# HeatpumpMonitor.net
KiCad netlist of a schematic drawn in EAGLE
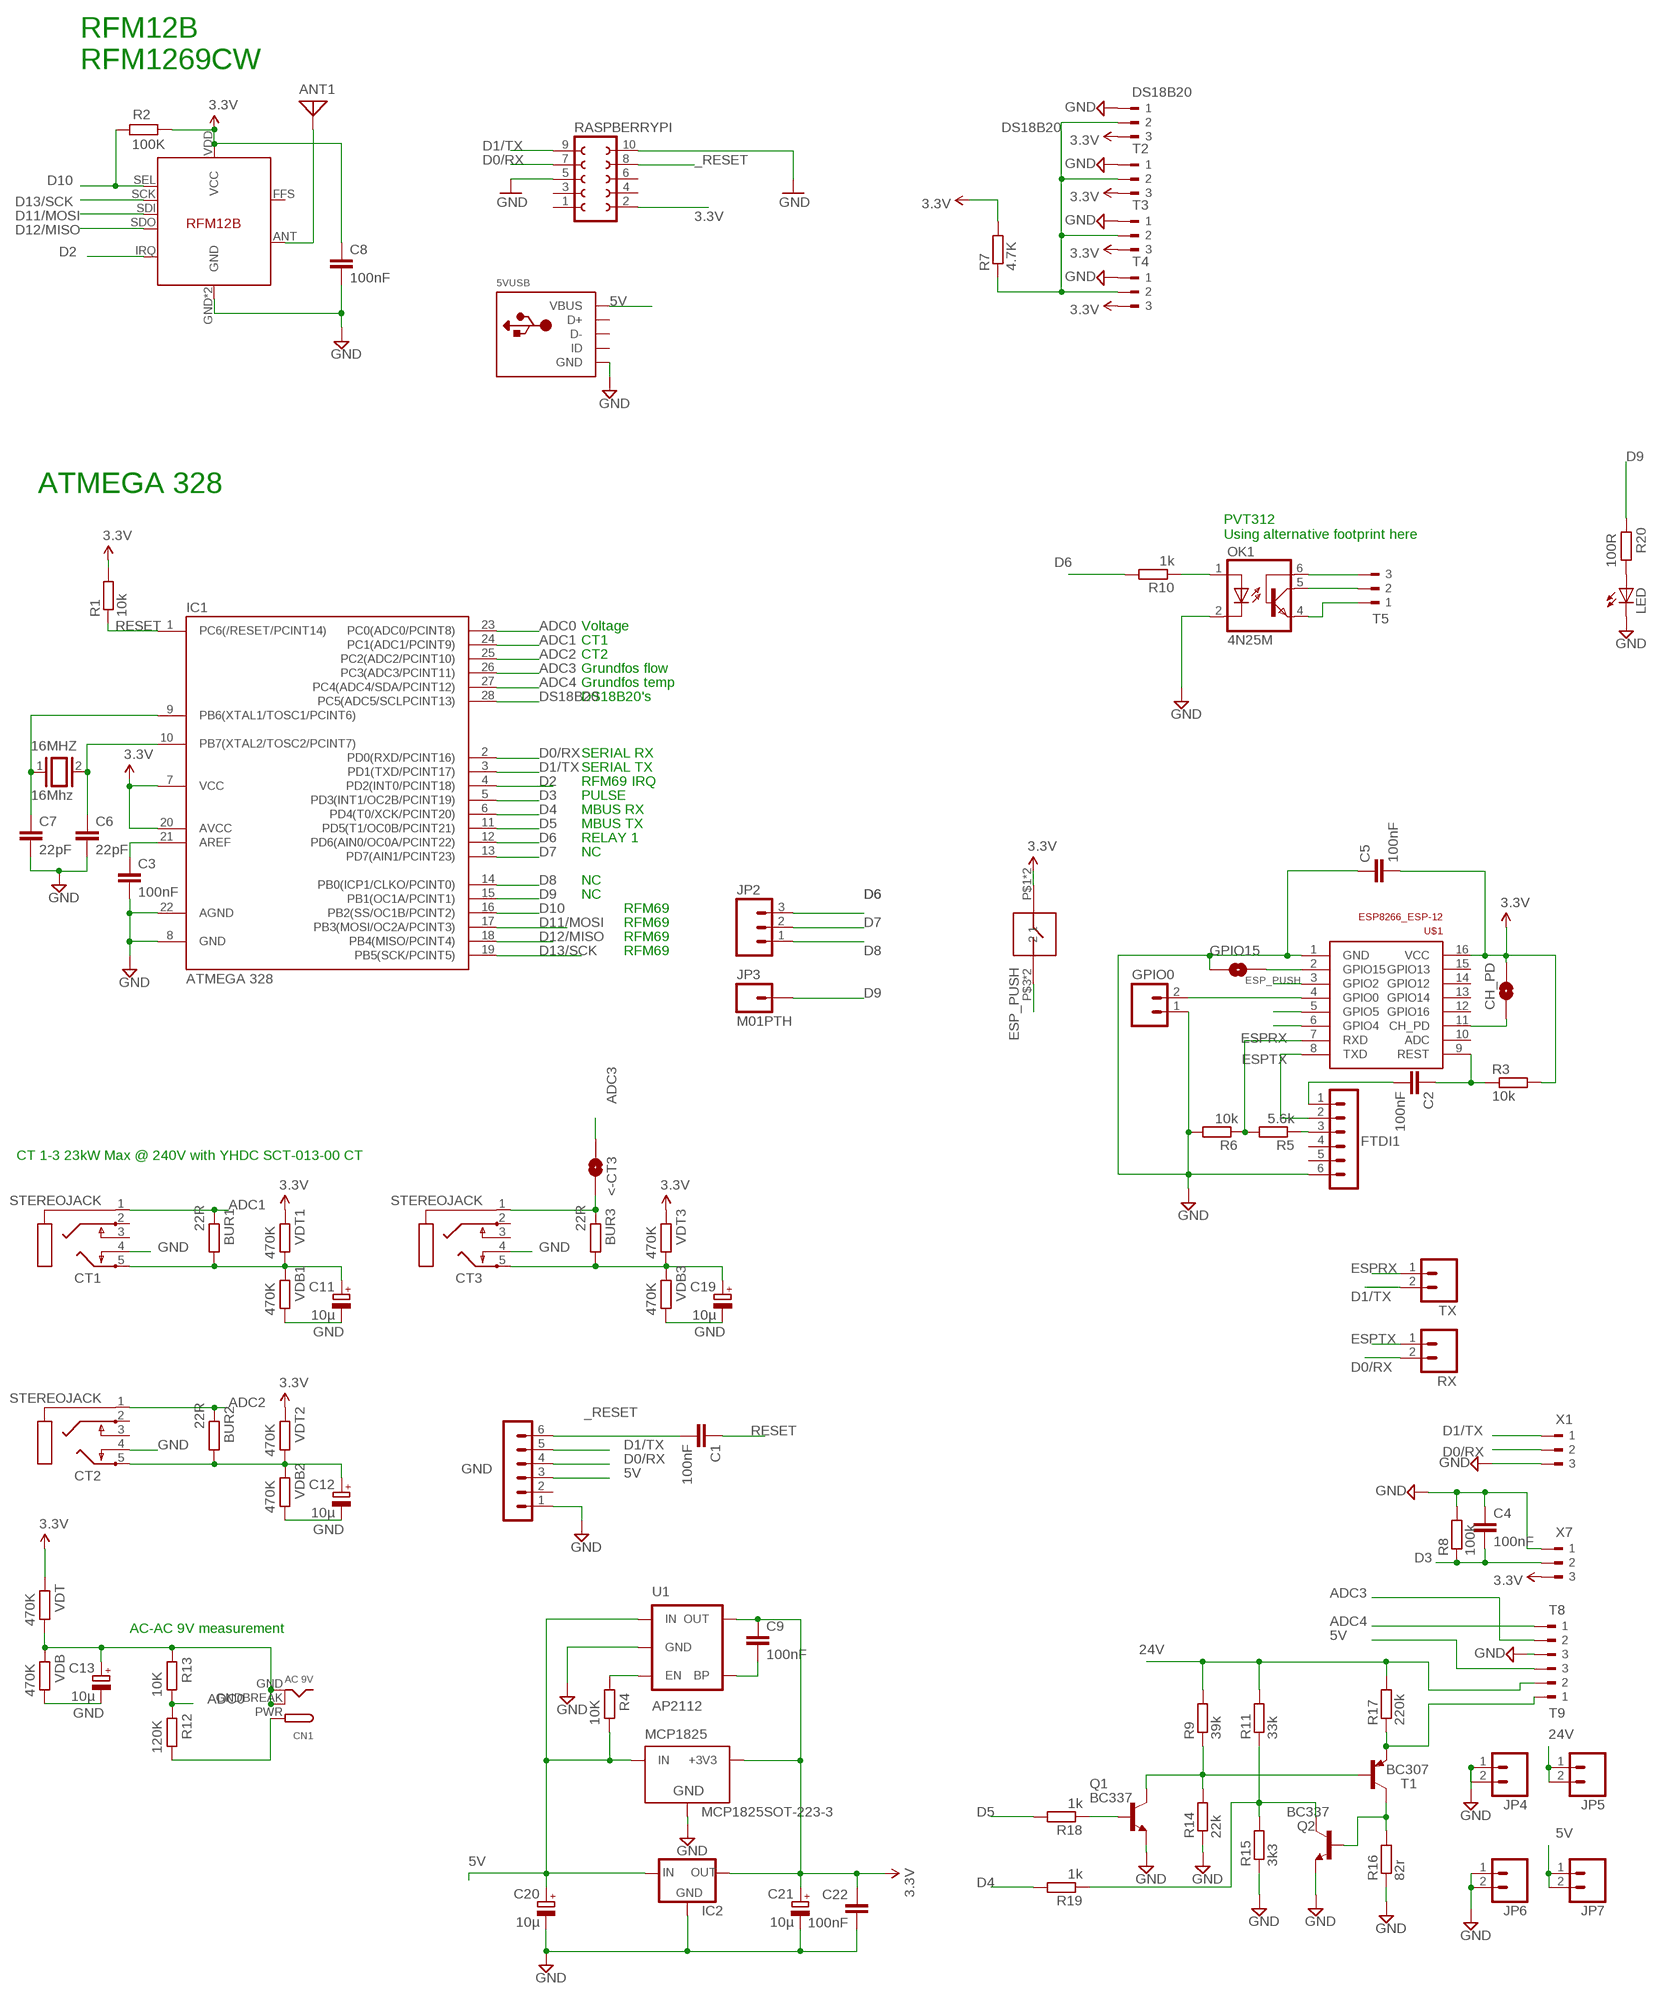
[diagram p0: schematic, sheet 1]

(export (version "E")
  (design (tool "Eeschema 10.0.6"))
  (components
    (comp (ref "5VUSB")
      (value "USBMOLEX")
      (footprint "eagle-import:USB-MINIB-THM-MOLEX")
      (libsource (lib "eagle-import") (part "USBMOLEX"))
    )
    (comp (ref "16MHZ")
      (value "16Mhz")
      (footprint "eagle-import:QS")
      (libsource (lib "eagle-import") (part "XTAL/S"))
    )
    (comp (ref "<-CT3")
      (value "SOLDERJUMPERNO")
      (footprint "eagle-import:SJ_2S-NO")
      (libsource (lib "eagle-import") (part "SOLDERJUMPERNO"))
    )
    (comp (ref "ANT1")
      (value "ANTENNA")
      (footprint "eagle-import:PAD-01")
      (libsource (lib "eagle-import") (part "ANTENNA"))
    )
    (comp (ref "BUR1")
      (value "22R")
      (footprint "eagle-import:0204_7")
      (libsource (lib "eagle-import") (part "R-EU_0204/7"))
    )
    (comp (ref "BUR2")
      (value "22R")
      (footprint "eagle-import:0204_7")
      (libsource (lib "eagle-import") (part "R-EU_0204/7"))
    )
    (comp (ref "BUR3")
      (value "22R")
      (footprint "eagle-import:0204_7")
      (libsource (lib "eagle-import") (part "R-EU_0204/7"))
    )
    (comp (ref "C1")
      (value "100nF")
      (footprint "eagle-import:C025-024X044")
      (libsource (lib "eagle-import") (part "C-EU025-024X044"))
    )
    (comp (ref "C2")
      (value "100nF")
      (footprint "eagle-import:C025-024X044")
      (libsource (lib "eagle-import") (part "C-EU025-024X044"))
    )
    (comp (ref "C3")
      (value "100nF")
      (footprint "eagle-import:C025-024X044")
      (libsource (lib "eagle-import") (part "C-EU025-024X044"))
    )
    (comp (ref "C4")
      (value "100nF")
      (footprint "eagle-import:C025-024X044")
      (libsource (lib "eagle-import") (part "C-EU025-024X044"))
    )
    (comp (ref "C5")
      (value "100nF")
      (footprint "eagle-import:C025-024X044")
      (libsource (lib "eagle-import") (part "C-EU025-024X044"))
    )
    (comp (ref "C6")
      (value "22pF")
      (footprint "eagle-import:C2.5-2")
      (libsource (lib "eagle-import") (part "C2.5/2"))
    )
    (comp (ref "C7")
      (value "22pF")
      (footprint "eagle-import:C2.5-2")
      (libsource (lib "eagle-import") (part "C2.5/2"))
    )
    (comp (ref "C8")
      (value "100nF")
      (footprint "eagle-import:C025-024X044")
      (libsource (lib "eagle-import") (part "C-EU025-024X044"))
    )
    (comp (ref "C9")
      (value "100nF")
      (footprint "eagle-import:C0603")
      (libsource (lib "eagle-import") (part "C-EUC0603"))
    )
    (comp (ref "C11")
      (value "10µ")
      (footprint "eagle-import:E1,8-4")
      (libsource (lib "eagle-import") (part "CPOL-EUE1.8-4"))
    )
    (comp (ref "C12")
      (value "10µ")
      (footprint "eagle-import:E1,8-4")
      (libsource (lib "eagle-import") (part "CPOL-EUE1.8-4"))
    )
    (comp (ref "C13")
      (value "10µ")
      (footprint "eagle-import:E1,8-4")
      (libsource (lib "eagle-import") (part "CPOL-EUE1.8-4"))
    )
    (comp (ref "C19")
      (value "10µ")
      (footprint "eagle-import:E1,8-4")
      (libsource (lib "eagle-import") (part "CPOL-EUE1.8-4"))
    )
    (comp (ref "C20")
      (value "10µ")
      (footprint "eagle-import:E1,8-4")
      (libsource (lib "eagle-import") (part "CPOL-EUE1.8-4"))
    )
    (comp (ref "C21")
      (value "10µ")
      (footprint "eagle-import:E1,8-4")
      (libsource (lib "eagle-import") (part "CPOL-EUE1.8-4"))
    )
    (comp (ref "C22")
      (value "100nF")
      (footprint "eagle-import:C025-024X044")
      (libsource (lib "eagle-import") (part "C-EU025-024X044"))
    )
    (comp (ref "CH_PD")
      (value "SOLDERJUMPERNO")
      (footprint "eagle-import:SJ_2S-NO")
      (libsource (lib "eagle-import") (part "SOLDERJUMPERNO"))
    )
    (comp (ref "CN1")
      (value "AC 9V")
      (footprint "eagle-import:DCJACK_2MM_PTH")
      (libsource (lib "eagle-import") (part "DCBARRELPTH"))
    )
    (comp (ref "CT1")
      (value "STEREOJACK")
      (footprint "eagle-import:STX3100")
      (libsource (lib "eagle-import") (part "STEREOJACK"))
    )
    (comp (ref "CT2")
      (value "STEREOJACK")
      (footprint "eagle-import:STX3100")
      (libsource (lib "eagle-import") (part "STEREOJACK"))
    )
    (comp (ref "CT3")
      (value "STEREOJACK")
      (footprint "eagle-import:STX3100")
      (libsource (lib "eagle-import") (part "STEREOJACK"))
    )
    (comp (ref "DS18B20")
      (value "180-3")
      (footprint "eagle-import:180-3")
      (libsource (lib "eagle-import") (part "180-3"))
    )
    (comp (ref "FTDI1")
      (value "FTDI")
      (footprint "eagle-import:MA06-1")
      (libsource (lib "eagle-import") (part "MA06-1"))
    )
    (comp (ref "GND")
      (value "FTDI")
      (footprint "eagle-import:MA06-1")
      (libsource (lib "eagle-import") (part "MA06-1"))
    )
    (comp (ref "GPIO0")
      (value "M02PTH")
      (footprint "eagle-import:1X02")
      (libsource (lib "eagle-import") (part "M02PTH"))
    )
    (comp (ref "GPIO15")
      (value "SOLDERJUMPERNO")
      (footprint "eagle-import:SJ_2S-NO")
      (libsource (lib "eagle-import") (part "SOLDERJUMPERNO"))
    )
    (comp (ref "IC1")
      (value "ATMEGA 328")
      (footprint "eagle-import:DIL28-3")
      (libsource (lib "eagle-import") (part "ATMEGA48/88/168-PU"))
    )
    (comp (ref "IC2")
      (value "78XXS")
      (footprint "eagle-import:78XXS")
      (libsource (lib "eagle-import") (part "78XXS"))
    )
    (comp (ref "JP2")
      (value "M03PTH")
      (footprint "eagle-import:1X03")
      (libsource (lib "eagle-import") (part "M03PTH"))
    )
    (comp (ref "JP3")
      (value "M01PTH")
      (footprint "eagle-import:1X01")
      (libsource (lib "eagle-import") (part "M01PTH"))
    )
    (comp (ref "JP4")
      (value "M02PTH")
      (footprint "eagle-import:1X02")
      (libsource (lib "eagle-import") (part "M02PTH"))
    )
    (comp (ref "JP5")
      (value "M02PTH")
      (footprint "eagle-import:1X02")
      (libsource (lib "eagle-import") (part "M02PTH"))
    )
    (comp (ref "JP6")
      (value "M02PTH")
      (footprint "eagle-import:1X02")
      (libsource (lib "eagle-import") (part "M02PTH"))
    )
    (comp (ref "JP7")
      (value "M02PTH")
      (footprint "eagle-import:1X02")
      (libsource (lib "eagle-import") (part "M02PTH"))
    )
    (comp (ref "LED")
      (value "LED3MM")
      (footprint "eagle-import:LED3MM")
      (libsource (lib "eagle-import") (part "LED3MM"))
    )
    (comp (ref "MCP1825")
      (value "MCP1825SOT-223-3")
      (footprint "eagle-import:SOT-223")
      (libsource (lib "eagle-import") (part "MCP1825SOT-223-3"))
    )
    (comp (ref "OK1")
      (value "4N25M")
      (footprint "eagle-import:DIL06")
      (fields (field (name "MPN") "4N25-M"))
      (libsource (lib "eagle-import") (part "4N?M25"))
    )
    (comp (ref "Q1")
      (value "BC337")
      (footprint "eagle-import:TO92")
      (libsource (lib "eagle-import") (part "BC337"))
    )
    (comp (ref "Q2")
      (value "BC337")
      (footprint "eagle-import:TO92")
      (libsource (lib "eagle-import") (part "BC337"))
    )
    (comp (ref "R1")
      (value "10k")
      (footprint "eagle-import:0204_7")
      (libsource (lib "eagle-import") (part "resistor_R-EU_0204/7"))
    )
    (comp (ref "R2")
      (value "100K")
      (footprint "eagle-import:0204_7")
      (libsource (lib "eagle-import") (part "R-EU_0204/7"))
    )
    (comp (ref "R3")
      (value "10k")
      (footprint "eagle-import:0204_7")
      (libsource (lib "eagle-import") (part "R-EU_0204/7"))
    )
    (comp (ref "R4")
      (value "10K")
      (footprint "eagle-import:R0603")
      (libsource (lib "eagle-import") (part "R-EU_R0603"))
    )
    (comp (ref "R5")
      (value "5.6k")
      (footprint "eagle-import:0204_7")
      (libsource (lib "eagle-import") (part "R-EU_0204/7"))
    )
    (comp (ref "R6")
      (value "10k")
      (footprint "eagle-import:0204_7")
      (libsource (lib "eagle-import") (part "R-EU_0204/7"))
    )
    (comp (ref "R7")
      (value "4.7K")
      (footprint "eagle-import:0204_7")
      (libsource (lib "eagle-import") (part "resistor_R-EU_0204/7"))
    )
    (comp (ref "R8")
      (value "100k")
      (footprint "eagle-import:0207_2V")
      (libsource (lib "eagle-import") (part "R-EU_0207/2V"))
    )
    (comp (ref "R9")
      (value "39k")
      (footprint "eagle-import:0204_7")
      (libsource (lib "eagle-import") (part "resistor_R-EU_0204/7"))
    )
    (comp (ref "R10")
      (value "1k")
      (footprint "eagle-import:0204_7")
      (libsource (lib "eagle-import") (part "R-EU_0204/7"))
    )
    (comp (ref "R11")
      (value "33k")
      (footprint "eagle-import:0204_7")
      (libsource (lib "eagle-import") (part "resistor_R-EU_0204/7"))
    )
    (comp (ref "R12")
      (value "120K")
      (footprint "eagle-import:0204_7")
      (libsource (lib "eagle-import") (part "R-EU_0204/7"))
    )
    (comp (ref "R13")
      (value "10K")
      (footprint "eagle-import:0204_7")
      (libsource (lib "eagle-import") (part "R-EU_0204/7"))
    )
    (comp (ref "R14")
      (value "22k")
      (footprint "eagle-import:0204_7")
      (libsource (lib "eagle-import") (part "resistor_R-EU_0204/7"))
    )
    (comp (ref "R15")
      (value "3k3")
      (footprint "eagle-import:0204_7")
      (libsource (lib "eagle-import") (part "resistor_R-EU_0204/7"))
    )
    (comp (ref "R16")
      (value "82r")
      (footprint "eagle-import:0204_7")
      (libsource (lib "eagle-import") (part "resistor_R-EU_0204/7"))
    )
    (comp (ref "R17")
      (value "220k")
      (footprint "eagle-import:0204_7")
      (libsource (lib "eagle-import") (part "resistor_R-EU_0204/7"))
    )
    (comp (ref "R18")
      (value "1k")
      (footprint "eagle-import:0204_7")
      (libsource (lib "eagle-import") (part "resistor_R-EU_0204/7"))
    )
    (comp (ref "R19")
      (value "1k")
      (footprint "eagle-import:0204_7")
      (libsource (lib "eagle-import") (part "resistor_R-EU_0204/7"))
    )
    (comp (ref "R20")
      (value "100R")
      (footprint "eagle-import:0204_7")
      (libsource (lib "eagle-import") (part "R-EU_0204/7"))
    )
    (comp (ref "RASPBERRYPI")
      (value "FE05-2")
      (footprint "eagle-import:FE05-2")
      (libsource (lib "eagle-import") (part "FE05-2"))
    )
    (comp (ref "RX")
      (value "M02PTH")
      (footprint "eagle-import:1X02")
      (libsource (lib "eagle-import") (part "M02PTH"))
    )
    (comp (ref "T1")
      (value "BC307")
      (footprint "eagle-import:TO92")
      (libsource (lib "eagle-import") (part "BC307"))
    )
    (comp (ref "T2")
      (value "180-3")
      (footprint "eagle-import:180-3")
      (libsource (lib "eagle-import") (part "180-3"))
    )
    (comp (ref "T3")
      (value "180-3")
      (footprint "eagle-import:180-3")
      (libsource (lib "eagle-import") (part "180-3"))
    )
    (comp (ref "T4")
      (value "180-3")
      (footprint "eagle-import:180-3")
      (libsource (lib "eagle-import") (part "180-3"))
    )
    (comp (ref "T5")
      (value "180-3")
      (footprint "eagle-import:180-3")
      (libsource (lib "eagle-import") (part "180-3"))
    )
    (comp (ref "T8")
      (value "180-3")
      (footprint "eagle-import:180-3")
      (libsource (lib "eagle-import") (part "180-3"))
    )
    (comp (ref "T9")
      (value "180-3")
      (footprint "eagle-import:180-3")
      (libsource (lib "eagle-import") (part "180-3"))
    )
    (comp (ref "TX")
      (value "M02PTH")
      (footprint "eagle-import:1X02")
      (libsource (lib "eagle-import") (part "M02PTH"))
    )
    (comp (ref "U$1")
      (value "ESP8266_ESP-12")
      (footprint "eagle-import:ESP8266-ESP12")
      (libsource (lib "eagle-import") (part "ESP8266_ESP-12"))
    )
    (comp (ref "U$2")
      (value "KSEK43G\"")
      (footprint "eagle-import:KSEK43G")
      (libsource (lib "eagle-import") (part "KSEK43G{dblquote}"))
    )
    (comp (ref "U$14")
      (value "RFM12B")
      (footprint "eagle-import:RFM12B")
      (libsource (lib "eagle-import") (part "RFM12B"))
    )
    (comp (ref "U1")
      (value "AP2112")
      (footprint "eagle-import:SOT23-5")
      (libsource (lib "eagle-import") (part "V_REG_LDOSMD"))
    )
    (comp (ref "VDB")
      (value "470K")
      (footprint "eagle-import:0204_7")
      (libsource (lib "eagle-import") (part "R-EU_0204/7"))
    )
    (comp (ref "VDB1")
      (value "470K")
      (footprint "eagle-import:0204_7")
      (libsource (lib "eagle-import") (part "R-EU_0204/7"))
    )
    (comp (ref "VDB2")
      (value "470K")
      (footprint "eagle-import:0204_7")
      (libsource (lib "eagle-import") (part "R-EU_0204/7"))
    )
    (comp (ref "VDB3")
      (value "470K")
      (footprint "eagle-import:0204_7")
      (libsource (lib "eagle-import") (part "R-EU_0204/7"))
    )
    (comp (ref "VDT")
      (value "470K")
      (footprint "eagle-import:0204_7")
      (libsource (lib "eagle-import") (part "R-EU_0204/7"))
    )
    (comp (ref "VDT1")
      (value "470K")
      (footprint "eagle-import:0204_7")
      (libsource (lib "eagle-import") (part "R-EU_0204/7"))
    )
    (comp (ref "VDT2")
      (value "470K")
      (footprint "eagle-import:0204_7")
      (libsource (lib "eagle-import") (part "R-EU_0204/7"))
    )
    (comp (ref "VDT3")
      (value "470K")
      (footprint "eagle-import:0204_7")
      (libsource (lib "eagle-import") (part "R-EU_0204/7"))
    )
    (comp (ref "X1")
      (value "180-3")
      (footprint "eagle-import:180-3")
      (libsource (lib "eagle-import") (part "180-3"))
    )
    (comp (ref "X7")
      (value "180-3")
      (footprint "eagle-import:180-3")
      (libsource (lib "eagle-import") (part "180-3"))
    )
  )
  (nets
    (net (code "1") (name "/5V") (class "Default")
      (node (ref "5VUSB") (pin "VBUS") (pinfunction "VBUS_VBUS") (pintype "power_in"))
      (node (ref "C20") (pin "+") (pinfunction "+_+") (pintype "passive"))
      (node (ref "GND") (pin "3") (pinfunction "3_3") (pintype "passive"))
      (node (ref "IC2") (pin "IN") (pinfunction "IN_IN") (pintype "input"))
      (node (ref "JP7") (pin "1") (pinfunction "1_1") (pintype "passive"))
      (node (ref "JP7") (pin "2") (pinfunction "2_2") (pintype "passive"))
      (node (ref "MCP1825") (pin "1") (pinfunction "IN_1") (pintype "power_in"))
      (node (ref "R4") (pin "1") (pinfunction "1_1") (pintype "passive"))
      (node (ref "T9") (pin "3") (pinfunction "3_3") (pintype "passive"))
      (node (ref "U1") (pin "1") (pinfunction "IN_1") (pintype "input"))
    )
    (net (code "2") (name "/24V") (class "Default")
      (node (ref "JP5") (pin "1") (pinfunction "1_1") (pintype "passive"))
      (node (ref "JP5") (pin "2") (pinfunction "2_2") (pintype "passive"))
      (node (ref "R11") (pin "2") (pinfunction "2_2") (pintype "passive"))
      (node (ref "R17") (pin "2") (pinfunction "2_2") (pintype "passive"))
      (node (ref "R9") (pin "2") (pinfunction "2_2") (pintype "passive"))
      (node (ref "T9") (pin "2") (pinfunction "2_2") (pintype "passive"))
    )
    (net (code "3") (name "/ADC0") (class "Default")
      (node (ref "IC1") (pin "23") (pinfunction "PC0(ADC0/PCINT8)_23") (pintype "bidirectional"))
      (node (ref "R12") (pin "2") (pinfunction "2_2") (pintype "passive"))
      (node (ref "R13") (pin "1") (pinfunction "1_1") (pintype "passive"))
    )
    (net (code "4") (name "/ADC1") (class "Default")
      (node (ref "BUR1") (pin "2") (pinfunction "2_2") (pintype "passive"))
      (node (ref "CT1") (pin "1") (pinfunction "1_1") (pintype "passive"))
      (node (ref "IC1") (pin "24") (pinfunction "PC1(ADC1/PCINT9)_24") (pintype "bidirectional"))
    )
    (net (code "5") (name "/ADC2") (class "Default")
      (node (ref "BUR2") (pin "2") (pinfunction "2_2") (pintype "passive"))
      (node (ref "CT2") (pin "1") (pinfunction "1_1") (pintype "passive"))
      (node (ref "IC1") (pin "25") (pinfunction "PC2(ADC2/PCINT10)_25") (pintype "bidirectional"))
    )
    (net (code "6") (name "/ADC3") (class "Default")
      (node (ref "<-CT3") (pin "2") (pinfunction "2_2") (pintype "passive"))
      (node (ref "IC1") (pin "26") (pinfunction "PC3(ADC3/PCINT11)_26") (pintype "bidirectional"))
      (node (ref "T8") (pin "2") (pinfunction "2_2") (pintype "passive"))
    )
    (net (code "7") (name "/ADC4") (class "Default")
      (node (ref "IC1") (pin "27") (pinfunction "PC4(ADC4/SDA/PCINT12)_27") (pintype "bidirectional"))
      (node (ref "T8") (pin "1") (pinfunction "1_1") (pintype "passive"))
    )
    (net (code "8") (name "/D0{slash}RX") (class "Default")
      (node (ref "GND") (pin "4") (pinfunction "4_4") (pintype "passive"))
      (node (ref "IC1") (pin "2") (pinfunction "PD0(RXD/PCINT16)_2") (pintype "bidirectional"))
      (node (ref "RASPBERRYPI") (pin "7") (pinfunction "7_7") (pintype "passive"))
      (node (ref "RX") (pin "2") (pinfunction "2_2") (pintype "passive"))
      (node (ref "X1") (pin "2") (pinfunction "2_2") (pintype "passive"))
    )
    (net (code "9") (name "/D1{slash}TX") (class "Default")
      (node (ref "GND") (pin "5") (pinfunction "5_5") (pintype "passive"))
      (node (ref "IC1") (pin "3") (pinfunction "PD1(TXD/PCINT17)_3") (pintype "bidirectional"))
      (node (ref "RASPBERRYPI") (pin "9") (pinfunction "9_9") (pintype "passive"))
      (node (ref "TX") (pin "2") (pinfunction "2_2") (pintype "passive"))
      (node (ref "X1") (pin "1") (pinfunction "1_1") (pintype "passive"))
    )
    (net (code "10") (name "/D2") (class "Default")
      (node (ref "IC1") (pin "4") (pinfunction "PD2(INT0/PCINT18)_4") (pintype "bidirectional"))
      (node (ref "U$14") (pin "IRQ") (pinfunction "IRQ_IRQ") (pintype "open_collector"))
    )
    (net (code "11") (name "/D3") (class "Default")
      (node (ref "C4") (pin "2") (pinfunction "2_2") (pintype "passive"))
      (node (ref "IC1") (pin "5") (pinfunction "PD3(INT1/OC2B/PCINT19)_5") (pintype "bidirectional"))
      (node (ref "R8") (pin "1") (pinfunction "1_1") (pintype "passive"))
      (node (ref "X7") (pin "2") (pinfunction "2_2") (pintype "passive"))
    )
    (net (code "12") (name "/D4") (class "Default")
      (node (ref "IC1") (pin "6") (pinfunction "PD4(T0/XCK/PCINT20)_6") (pintype "bidirectional"))
      (node (ref "R19") (pin "2") (pinfunction "2_2") (pintype "passive"))
    )
    (net (code "13") (name "/D5") (class "Default")
      (node (ref "IC1") (pin "11") (pinfunction "PD5(T1/OC0B/PCINT21)_11") (pintype "bidirectional"))
      (node (ref "R18") (pin "2") (pinfunction "2_2") (pintype "passive"))
    )
    (net (code "14") (name "/D6") (class "Default")
      (node (ref "IC1") (pin "12") (pinfunction "PD6(AIN0/OC0A/PCINT22)_12") (pintype "bidirectional"))
      (node (ref "JP2") (pin "3") (pinfunction "3_3") (pintype "passive"))
      (node (ref "R10") (pin "2") (pinfunction "2_2") (pintype "passive"))
    )
    (net (code "15") (name "/D7") (class "Default")
      (node (ref "IC1") (pin "13") (pinfunction "PD7(AIN1/PCINT23)_13") (pintype "bidirectional"))
      (node (ref "JP2") (pin "2") (pinfunction "2_2") (pintype "passive"))
    )
    (net (code "16") (name "/D8") (class "Default")
      (node (ref "IC1") (pin "14") (pinfunction "PB0(ICP1/CLKO/PCINT0)_14") (pintype "bidirectional"))
      (node (ref "JP2") (pin "1") (pinfunction "1_1") (pintype "passive"))
    )
    (net (code "17") (name "/D9") (class "Default")
      (node (ref "IC1") (pin "15") (pinfunction "PB1(OC1A/PCINT1)_15") (pintype "bidirectional"))
      (node (ref "JP3") (pin "1") (pinfunction "1_1") (pintype "passive"))
      (node (ref "R20") (pin "2") (pinfunction "2_2") (pintype "passive"))
    )
    (net (code "18") (name "/D10") (class "Default")
      (node (ref "IC1") (pin "16") (pinfunction "PB2(SS/OC1B/PCINT2)_16") (pintype "bidirectional"))
      (node (ref "R2") (pin "2") (pinfunction "2_2") (pintype "passive"))
      (node (ref "U$14") (pin "SEL") (pinfunction "SEL_SEL") (pintype "input"))
    )
    (net (code "19") (name "/D11{slash}MOSI") (class "Default")
      (node (ref "IC1") (pin "17") (pinfunction "PB3(MOSI/OC2A/PCINT3)_17") (pintype "bidirectional"))
      (node (ref "U$14") (pin "SDI") (pinfunction "SDI_SDI") (pintype "input"))
    )
    (net (code "20") (name "/D12{slash}MISO") (class "Default")
      (node (ref "IC1") (pin "18") (pinfunction "PB4(MISO/PCINT4)_18") (pintype "bidirectional"))
      (node (ref "U$14") (pin "SDO") (pinfunction "SDO_SDO") (pintype "output"))
    )
    (net (code "21") (name "/D13{slash}SCK") (class "Default")
      (node (ref "IC1") (pin "19") (pinfunction "PB5(SCK/PCINT5)_19") (pintype "bidirectional"))
      (node (ref "U$14") (pin "SCK") (pinfunction "SCK_SCK") (pintype "input"))
    )
    (net (code "22") (name "/DS18B20") (class "Default")
      (node (ref "DS18B20") (pin "2") (pinfunction "2_2") (pintype "passive"))
      (node (ref "IC1") (pin "28") (pinfunction "PC5(ADC5/SCLPCINT13)_28") (pintype "bidirectional"))
      (node (ref "R7") (pin "1") (pinfunction "1_1") (pintype "passive"))
      (node (ref "T2") (pin "2") (pinfunction "2_2") (pintype "passive"))
      (node (ref "T3") (pin "2") (pinfunction "2_2") (pintype "passive"))
      (node (ref "T4") (pin "2") (pinfunction "2_2") (pintype "passive"))
    )
    (net (code "23") (name "/ESPRX") (class "Default")
      (node (ref "R5") (pin "2") (pinfunction "2_2") (pintype "passive"))
      (node (ref "R6") (pin "1") (pinfunction "1_1") (pintype "passive"))
      (node (ref "TX") (pin "1") (pinfunction "1_1") (pintype "passive"))
      (node (ref "U$1") (pin "7") (pinfunction "RXD_7") (pintype "bidirectional"))
    )
    (net (code "24") (name "/ESPTX") (class "Default")
      (node (ref "FTDI1") (pin "2") (pinfunction "2_2") (pintype "passive"))
      (node (ref "RX") (pin "1") (pinfunction "1_1") (pintype "passive"))
      (node (ref "U$1") (pin "8") (pinfunction "TXD_8") (pintype "bidirectional"))
    )
    (net (code "25") (name "/ESP_PUSH") (class "Default")
      (node (ref "U$1") (pin "3") (pinfunction "GPIO2_3") (pintype "bidirectional"))
      (node (ref "U$2") (pin "P$3") (pinfunction "2_P$3") (pintype "bidirectional"))
      (node (ref "U$2") (pin "P$4") (pinfunction "2_P$4") (pintype "bidirectional"))
    )
    (net (code "26") (name "/RESET") (class "Default")
      (node (ref "C1") (pin "1") (pinfunction "1_1") (pintype "passive"))
      (node (ref "IC1") (pin "1") (pinfunction "PC6(/RESET/PCINT14)_1") (pintype "bidirectional"))
      (node (ref "R1") (pin "1") (pinfunction "1_1") (pintype "passive"))
    )
    (net (code "27") (name "/_RESET") (class "Default")
      (node (ref "C1") (pin "2") (pinfunction "2_2") (pintype "passive"))
      (node (ref "GND") (pin "6") (pinfunction "6_6") (pintype "passive"))
      (node (ref "RASPBERRYPI") (pin "8") (pinfunction "8_8") (pintype "passive"))
    )
    (net (code "28") (name "3.3V") (class "Default")
      (node (ref "C21") (pin "+") (pinfunction "+_+") (pintype "passive"))
      (node (ref "C22") (pin "1") (pinfunction "1_1") (pintype "passive"))
      (node (ref "C5") (pin "2") (pinfunction "2_2") (pintype "passive"))
      (node (ref "C8") (pin "1") (pinfunction "1_1") (pintype "passive"))
      (node (ref "C9") (pin "1") (pinfunction "1_1") (pintype "passive"))
      (node (ref "CH_PD") (pin "1") (pinfunction "1_1") (pintype "passive"))
      (node (ref "DS18B20") (pin "3") (pinfunction "3_3") (pintype "passive"))
      (node (ref "IC1") (pin "20") (pinfunction "AVCC_20") (pintype "passive"))
      (node (ref "IC1") (pin "7") (pinfunction "VCC_7") (pintype "power_in"))
      (node (ref "IC2") (pin "OUT") (pinfunction "OUT_OUT") (pintype "passive"))
      (node (ref "MCP1825") (pin "3") (pinfunction "+3V3_3") (pintype "power_in"))
      (node (ref "R1") (pin "2") (pinfunction "2_2") (pintype "passive"))
      (node (ref "R2") (pin "1") (pinfunction "1_1") (pintype "passive"))
      (node (ref "R3") (pin "2") (pinfunction "2_2") (pintype "passive"))
      (node (ref "R7") (pin "2") (pinfunction "2_2") (pintype "passive"))
      (node (ref "RASPBERRYPI") (pin "2") (pinfunction "2_2") (pintype "passive"))
      (node (ref "T2") (pin "3") (pinfunction "3_3") (pintype "passive"))
      (node (ref "T3") (pin "3") (pinfunction "3_3") (pintype "passive"))
      (node (ref "T4") (pin "3") (pinfunction "3_3") (pintype "passive"))
      (node (ref "U$1") (pin "16") (pinfunction "VCC_16") (pintype "bidirectional"))
      (node (ref "U$14") (pin "VDD") (pinfunction "VCC_VDD") (pintype "power_in"))
      (node (ref "U$2") (pin "P$1") (pinfunction "1_P$1") (pintype "bidirectional"))
      (node (ref "U$2") (pin "P$2") (pinfunction "1_P$2") (pintype "bidirectional"))
      (node (ref "U1") (pin "5") (pinfunction "OUT_5") (pintype "passive"))
      (node (ref "VDT") (pin "2") (pinfunction "2_2") (pintype "passive"))
      (node (ref "VDT1") (pin "2") (pinfunction "2_2") (pintype "passive"))
      (node (ref "VDT2") (pin "2") (pinfunction "2_2") (pintype "passive"))
      (node (ref "VDT3") (pin "2") (pinfunction "2_2") (pintype "passive"))
      (node (ref "X7") (pin "3") (pinfunction "3_3") (pintype "passive"))
    )
    (net (code "29") (name "GND") (class "Default")
      (node (ref "5VUSB") (pin "GND") (pinfunction "GND_GND") (pintype "power_in"))
      (node (ref "C11") (pin "-") (pinfunction "-_-") (pintype "passive"))
      (node (ref "C12") (pin "-") (pinfunction "-_-") (pintype "passive"))
      (node (ref "C13") (pin "-") (pinfunction "-_-") (pintype "passive"))
      (node (ref "C19") (pin "-") (pinfunction "-_-") (pintype "passive"))
      (node (ref "C20") (pin "-") (pinfunction "-_-") (pintype "passive"))
      (node (ref "C21") (pin "-") (pinfunction "-_-") (pintype "passive"))
      (node (ref "C22") (pin "2") (pinfunction "2_2") (pintype "passive"))
      (node (ref "C3") (pin "2") (pinfunction "2_2") (pintype "passive"))
      (node (ref "C4") (pin "1") (pinfunction "1_1") (pintype "passive"))
      (node (ref "C5") (pin "1") (pinfunction "1_1") (pintype "passive"))
      (node (ref "C6") (pin "2") (pinfunction "2_2") (pintype "passive"))
      (node (ref "C7") (pin "2") (pinfunction "2_2") (pintype "passive"))
      (node (ref "C8") (pin "2") (pinfunction "2_2") (pintype "passive"))
      (node (ref "CT1") (pin "4") (pinfunction "4_4") (pintype "passive"))
      (node (ref "CT2") (pin "4") (pinfunction "4_4") (pintype "passive"))
      (node (ref "CT3") (pin "4") (pinfunction "4_4") (pintype "passive"))
      (node (ref "DS18B20") (pin "1") (pinfunction "1_1") (pintype "passive"))
      (node (ref "FTDI1") (pin "6") (pinfunction "6_6") (pintype "passive"))
      (node (ref "GND") (pin "1") (pinfunction "1_1") (pintype "passive"))
      (node (ref "GPIO0") (pin "1") (pinfunction "1_1") (pintype "passive"))
      (node (ref "GPIO15") (pin "2") (pinfunction "2_2") (pintype "passive"))
      (node (ref "IC1") (pin "22") (pinfunction "AGND_22") (pintype "power_in"))
      (node (ref "IC1") (pin "8") (pinfunction "GND_8") (pintype "power_in"))
      (node (ref "IC2") (pin "GND") (pinfunction "GND_GND") (pintype "input"))
      (node (ref "JP4") (pin "1") (pinfunction "1_1") (pintype "passive"))
      (node (ref "JP4") (pin "2") (pinfunction "2_2") (pintype "passive"))
      (node (ref "JP6") (pin "1") (pinfunction "1_1") (pintype "passive"))
      (node (ref "JP6") (pin "2") (pinfunction "2_2") (pintype "passive"))
      (node (ref "LED") (pin "K") (pinfunction "C_K") (pintype "passive"))
      (node (ref "MCP1825") (pin "2") (pinfunction "GND_2") (pintype "power_in"))
      (node (ref "OK1") (pin "2") (pinfunction "C_2") (pintype "passive"))
      (node (ref "Q1") (pin "1") (pinfunction "E_1") (pintype "passive"))
      (node (ref "Q2") (pin "1") (pinfunction "E_1") (pintype "passive"))
      (node (ref "R14") (pin "1") (pinfunction "1_1") (pintype "passive"))
      (node (ref "R15") (pin "1") (pinfunction "1_1") (pintype "passive"))
      (node (ref "R16") (pin "1") (pinfunction "1_1") (pintype "passive"))
      (node (ref "R6") (pin "2") (pinfunction "2_2") (pintype "passive"))
      (node (ref "R8") (pin "2") (pinfunction "2_2") (pintype "passive"))
      (node (ref "RASPBERRYPI") (pin "10") (pinfunction "10_10") (pintype "passive"))
      (node (ref "RASPBERRYPI") (pin "5") (pinfunction "5_5") (pintype "passive"))
      (node (ref "T2") (pin "1") (pinfunction "1_1") (pintype "passive"))
      (node (ref "T3") (pin "1") (pinfunction "1_1") (pintype "passive"))
      (node (ref "T4") (pin "1") (pinfunction "1_1") (pintype "passive"))
      (node (ref "T8") (pin "3") (pinfunction "3_3") (pintype "passive"))
      (node (ref "U$1") (pin "1") (pinfunction "GND_1") (pintype "bidirectional"))
      (node (ref "U$14") (pin "GND") (pinfunction "GND_GND") (pintype "power_in"))
      (node (ref "U$14") (pin "P$12") (pinfunction "GND_P$12") (pintype "power_in"))
      (node (ref "U1") (pin "2") (pinfunction "GND_2") (pintype "input"))
      (node (ref "VDB") (pin "1") (pinfunction "1_1") (pintype "passive"))
      (node (ref "VDB1") (pin "1") (pinfunction "1_1") (pintype "passive"))
      (node (ref "VDB2") (pin "1") (pinfunction "1_1") (pintype "passive"))
      (node (ref "VDB3") (pin "1") (pinfunction "1_1") (pintype "passive"))
      (node (ref "X1") (pin "3") (pinfunction "3_3") (pintype "passive"))
      (node (ref "X7") (pin "1") (pinfunction "1_1") (pintype "passive"))
    )
    (net (code "30") (name "Net-(<-CT3-Pad1)") (class "Default")
      (node (ref "<-CT3") (pin "1") (pinfunction "1_1") (pintype "passive"))
      (node (ref "BUR3") (pin "2") (pinfunction "2_2") (pintype "passive"))
      (node (ref "CT3") (pin "1") (pinfunction "1_1") (pintype "passive"))
    )
    (net (code "31") (name "Net-(ANT1-Pad1)") (class "Default")
      (node (ref "ANT1") (pin "1") (pinfunction "1_1") (pintype "output"))
      (node (ref "U$14") (pin "ANT") (pinfunction "ANT_ANT") (pintype "passive"))
    )
    (net (code "32") (name "Net-(BUR1-Pad1)") (class "Default")
      (node (ref "BUR1") (pin "1") (pinfunction "1_1") (pintype "passive"))
      (node (ref "C11") (pin "+") (pinfunction "+_+") (pintype "passive"))
      (node (ref "CT1") (pin "5") (pinfunction "5_5") (pintype "passive"))
      (node (ref "VDB1") (pin "2") (pinfunction "2_2") (pintype "passive"))
      (node (ref "VDT1") (pin "1") (pinfunction "1_1") (pintype "passive"))
    )
    (net (code "33") (name "Net-(BUR2-Pad1)") (class "Default")
      (node (ref "BUR2") (pin "1") (pinfunction "1_1") (pintype "passive"))
      (node (ref "C12") (pin "+") (pinfunction "+_+") (pintype "passive"))
      (node (ref "CT2") (pin "5") (pinfunction "5_5") (pintype "passive"))
      (node (ref "VDB2") (pin "2") (pinfunction "2_2") (pintype "passive"))
      (node (ref "VDT2") (pin "1") (pinfunction "1_1") (pintype "passive"))
    )
    (net (code "34") (name "Net-(BUR3-Pad1)") (class "Default")
      (node (ref "BUR3") (pin "1") (pinfunction "1_1") (pintype "passive"))
      (node (ref "C19") (pin "+") (pinfunction "+_+") (pintype "passive"))
      (node (ref "CT3") (pin "5") (pinfunction "5_5") (pintype "passive"))
      (node (ref "VDB3") (pin "2") (pinfunction "2_2") (pintype "passive"))
      (node (ref "VDT3") (pin "1") (pinfunction "1_1") (pintype "passive"))
    )
    (net (code "35") (name "Net-(C2-Pad2)") (class "Default")
      (node (ref "C2") (pin "2") (pinfunction "2_2") (pintype "passive"))
      (node (ref "FTDI1") (pin "1") (pinfunction "1_1") (pintype "passive"))
    )
    (net (code "36") (name "Net-(C13-Pad+)") (class "Default")
      (node (ref "C13") (pin "+") (pinfunction "+_+") (pintype "passive"))
      (node (ref "CN1") (pin "GND") (pinfunction "GND_GND") (pintype "power_in"))
      (node (ref "CN1") (pin "GNDBREAK") (pinfunction "GNDBREAK_GNDBREAK") (pintype "power_in"))
      (node (ref "R13") (pin "2") (pinfunction "2_2") (pintype "passive"))
      (node (ref "VDB") (pin "2") (pinfunction "2_2") (pintype "passive"))
      (node (ref "VDT") (pin "1") (pinfunction "1_1") (pintype "passive"))
    )
    (net (code "37") (name "Net-(CN1-PadPWR)") (class "Default")
      (node (ref "CN1") (pin "PWR") (pinfunction "PWR_PWR") (pintype "power_in"))
      (node (ref "R12") (pin "1") (pinfunction "1_1") (pintype "passive"))
    )
    (net (code "38") (name "Net-(FTDI1-Pad3)") (class "Default")
      (node (ref "FTDI1") (pin "3") (pinfunction "3_3") (pintype "passive"))
      (node (ref "R5") (pin "1") (pinfunction "1_1") (pintype "passive"))
    )
    (net (code "39") (name "Net-(IC1-AREF)") (class "Default")
      (node (ref "C3") (pin "1") (pinfunction "1_1") (pintype "passive"))
      (node (ref "IC1") (pin "21") (pinfunction "AREF_21") (pintype "passive"))
    )
    (net (code "40") (name "Net-(IC1-PB6(XTAL1{slash}TOSC1{slash}PCINT6))") (class "Default")
      (node (ref "16MHZ") (pin "1") (pinfunction "1_1") (pintype "passive"))
      (node (ref "C7") (pin "1") (pinfunction "1_1") (pintype "passive"))
      (node (ref "IC1") (pin "9") (pinfunction "PB6(XTAL1/TOSC1/PCINT6)_9") (pintype "bidirectional"))
    )
    (net (code "41") (name "Net-(IC1-PB7(XTAL2{slash}TOSC2{slash}PCINT7))") (class "Default")
      (node (ref "16MHZ") (pin "2") (pinfunction "2_2") (pintype "passive"))
      (node (ref "C6") (pin "1") (pinfunction "1_1") (pintype "passive"))
      (node (ref "IC1") (pin "10") (pinfunction "PB7(XTAL2/TOSC2/PCINT7)_10") (pintype "bidirectional"))
    )
    (net (code "42") (name "Net-(LED-PadA)") (class "Default")
      (node (ref "LED") (pin "A") (pinfunction "A_A") (pintype "passive"))
      (node (ref "R20") (pin "1") (pinfunction "1_1") (pintype "passive"))
    )
    (net (code "43") (name "Net-(OK1-A)") (class "Default")
      (node (ref "OK1") (pin "1") (pinfunction "A_1") (pintype "passive"))
      (node (ref "R10") (pin "1") (pinfunction "1_1") (pintype "passive"))
    )
    (net (code "44") (name "Net-(OK1-BAS)") (class "Default")
      (node (ref "OK1") (pin "6") (pinfunction "BAS_6") (pintype "passive"))
      (node (ref "T5") (pin "3") (pinfunction "3_3") (pintype "passive"))
    )
    (net (code "45") (name "Net-(OK1-COL)") (class "Default")
      (node (ref "OK1") (pin "5") (pinfunction "COL_5") (pintype "passive"))
      (node (ref "T5") (pin "2") (pinfunction "2_2") (pintype "passive"))
    )
    (net (code "46") (name "Net-(OK1-EMI)") (class "Default")
      (node (ref "OK1") (pin "4") (pinfunction "EMI_4") (pintype "passive"))
      (node (ref "T5") (pin "1") (pinfunction "1_1") (pintype "passive"))
    )
    (net (code "47") (name "Net-(Q1-B)") (class "Default")
      (node (ref "Q1") (pin "2") (pinfunction "B_2") (pintype "passive"))
      (node (ref "R18") (pin "1") (pinfunction "1_1") (pintype "passive"))
    )
    (net (code "48") (name "Net-(Q1-C)") (class "Default")
      (node (ref "Q1") (pin "3") (pinfunction "C_3") (pintype "passive"))
      (node (ref "R14") (pin "2") (pinfunction "2_2") (pintype "passive"))
      (node (ref "R9") (pin "1") (pinfunction "1_1") (pintype "passive"))
      (node (ref "T1") (pin "2") (pinfunction "B_2") (pintype "passive"))
    )
    (net (code "49") (name "Net-(Q2-B)") (class "Default")
      (node (ref "Q2") (pin "2") (pinfunction "B_2") (pintype "passive"))
      (node (ref "R16") (pin "2") (pinfunction "2_2") (pintype "passive"))
      (node (ref "T1") (pin "3") (pinfunction "C_3") (pintype "passive"))
    )
    (net (code "50") (name "Net-(Q2-C)") (class "Default")
      (node (ref "Q2") (pin "3") (pinfunction "C_3") (pintype "passive"))
      (node (ref "R11") (pin "1") (pinfunction "1_1") (pintype "passive"))
      (node (ref "R15") (pin "2") (pinfunction "2_2") (pintype "passive"))
      (node (ref "R19") (pin "1") (pinfunction "1_1") (pintype "passive"))
    )
    (net (code "51") (name "Net-(T1-E)") (class "Default")
      (node (ref "R17") (pin "1") (pinfunction "1_1") (pintype "passive"))
      (node (ref "T1") (pin "1") (pinfunction "E_1") (pintype "passive"))
      (node (ref "T9") (pin "1") (pinfunction "1_1") (pintype "passive"))
    )
    (net (code "52") (name "Net-(U$1-CH_PD)") (class "Default")
      (node (ref "CH_PD") (pin "2") (pinfunction "2_2") (pintype "passive"))
      (node (ref "U$1") (pin "11") (pinfunction "CH_PD_11") (pintype "bidirectional"))
    )
    (net (code "53") (name "Net-(U$1-GPIO0)") (class "Default")
      (node (ref "GPIO0") (pin "2") (pinfunction "2_2") (pintype "passive"))
      (node (ref "U$1") (pin "4") (pinfunction "GPIO0_4") (pintype "bidirectional"))
    )
    (net (code "54") (name "Net-(U$1-GPIO15)") (class "Default")
      (node (ref "GPIO15") (pin "1") (pinfunction "1_1") (pintype "passive"))
      (node (ref "U$1") (pin "2") (pinfunction "GPIO15_2") (pintype "bidirectional"))
    )
    (net (code "55") (name "Net-(U$1-REST)") (class "Default")
      (node (ref "C2") (pin "1") (pinfunction "1_1") (pintype "passive"))
      (node (ref "R3") (pin "1") (pinfunction "1_1") (pintype "passive"))
      (node (ref "U$1") (pin "9") (pinfunction "REST_9") (pintype "bidirectional"))
    )
    (net (code "56") (name "Net-(U1-BP)") (class "Default")
      (node (ref "C9") (pin "2") (pinfunction "2_2") (pintype "passive"))
      (node (ref "U1") (pin "4") (pinfunction "BP_4") (pintype "input"))
    )
    (net (code "57") (name "Net-(U1-EN)") (class "Default")
      (node (ref "R4") (pin "2") (pinfunction "2_2") (pintype "passive"))
      (node (ref "U1") (pin "3") (pinfunction "EN_3") (pintype "input"))
    )
    (net (code "58") (name "unconnected-(5VUSB-PadD+)") (class "Default")
      (node (ref "5VUSB") (pin "D+") (pinfunction "D+_D+") (pintype "bidirectional"))
    )
    (net (code "59") (name "unconnected-(5VUSB-PadD-)") (class "Default")
      (node (ref "5VUSB") (pin "D-") (pinfunction "D-_D-") (pintype "bidirectional"))
    )
    (net (code "60") (name "unconnected-(5VUSB-PadID)") (class "Default")
      (node (ref "5VUSB") (pin "ID") (pinfunction "ID_ID") (pintype "bidirectional"))
    )
    (net (code "61") (name "unconnected-(CT1-Pad2)") (class "Default")
      (node (ref "CT1") (pin "2") (pinfunction "2_2") (pintype "passive"))
    )
    (net (code "62") (name "unconnected-(CT1-Pad3)") (class "Default")
      (node (ref "CT1") (pin "3") (pinfunction "3_3") (pintype "passive"))
    )
    (net (code "63") (name "unconnected-(CT2-Pad2)") (class "Default")
      (node (ref "CT2") (pin "2") (pinfunction "2_2") (pintype "passive"))
    )
    (net (code "64") (name "unconnected-(CT2-Pad3)") (class "Default")
      (node (ref "CT2") (pin "3") (pinfunction "3_3") (pintype "passive"))
    )
    (net (code "65") (name "unconnected-(CT3-Pad2)") (class "Default")
      (node (ref "CT3") (pin "2") (pinfunction "2_2") (pintype "passive"))
    )
    (net (code "66") (name "unconnected-(CT3-Pad3)") (class "Default")
      (node (ref "CT3") (pin "3") (pinfunction "3_3") (pintype "passive"))
    )
    (net (code "67") (name "unconnected-(FTDI1-Pad4)") (class "Default")
      (node (ref "FTDI1") (pin "4") (pinfunction "4_4") (pintype "passive"))
    )
    (net (code "68") (name "unconnected-(FTDI1-Pad5)") (class "Default")
      (node (ref "FTDI1") (pin "5") (pinfunction "5_5") (pintype "passive"))
    )
    (net (code "69") (name "unconnected-(GND-Pad2)") (class "Default")
      (node (ref "GND") (pin "2") (pinfunction "2_2") (pintype "passive"))
    )
    (net (code "70") (name "unconnected-(RASPBERRYPI-Pad1)") (class "Default")
      (node (ref "RASPBERRYPI") (pin "1") (pinfunction "1_1") (pintype "passive"))
    )
    (net (code "71") (name "unconnected-(RASPBERRYPI-Pad3)") (class "Default")
      (node (ref "RASPBERRYPI") (pin "3") (pinfunction "3_3") (pintype "passive"))
    )
    (net (code "72") (name "unconnected-(RASPBERRYPI-Pad4)") (class "Default")
      (node (ref "RASPBERRYPI") (pin "4") (pinfunction "4_4") (pintype "passive"))
    )
    (net (code "73") (name "unconnected-(RASPBERRYPI-Pad6)") (class "Default")
      (node (ref "RASPBERRYPI") (pin "6") (pinfunction "6_6") (pintype "passive"))
    )
    (net (code "74") (name "unconnected-(U$1-ADC-Pad10)") (class "Default")
      (node (ref "U$1") (pin "10") (pinfunction "ADC_10") (pintype "bidirectional"))
    )
    (net (code "75") (name "unconnected-(U$1-GPIO4-Pad6)") (class "Default")
      (node (ref "U$1") (pin "6") (pinfunction "GPIO4_6") (pintype "bidirectional"))
    )
    (net (code "76") (name "unconnected-(U$1-GPIO5-Pad5)") (class "Default")
      (node (ref "U$1") (pin "5") (pinfunction "GPIO5_5") (pintype "bidirectional"))
    )
    (net (code "77") (name "unconnected-(U$1-GPIO12-Pad14)") (class "Default")
      (node (ref "U$1") (pin "14") (pinfunction "GPIO12_14") (pintype "bidirectional"))
    )
    (net (code "78") (name "unconnected-(U$1-GPIO13-Pad15)") (class "Default")
      (node (ref "U$1") (pin "15") (pinfunction "GPIO13_15") (pintype "bidirectional"))
    )
    (net (code "79") (name "unconnected-(U$1-GPIO14-Pad13)") (class "Default")
      (node (ref "U$1") (pin "13") (pinfunction "GPIO14_13") (pintype "bidirectional"))
    )
    (net (code "80") (name "unconnected-(U$1-GPIO16-Pad12)") (class "Default")
      (node (ref "U$1") (pin "12") (pinfunction "GPIO16_12") (pintype "bidirectional"))
    )
    (net (code "81") (name "unconnected-(U$14-PadFFS)") (class "Default")
      (node (ref "U$14") (pin "FFS") (pinfunction "FFS_FFS") (pintype "bidirectional"))
    )
  )
)
